# 06_SDIO.net
KiCad netlist of a schematic drawn in Altium Designer
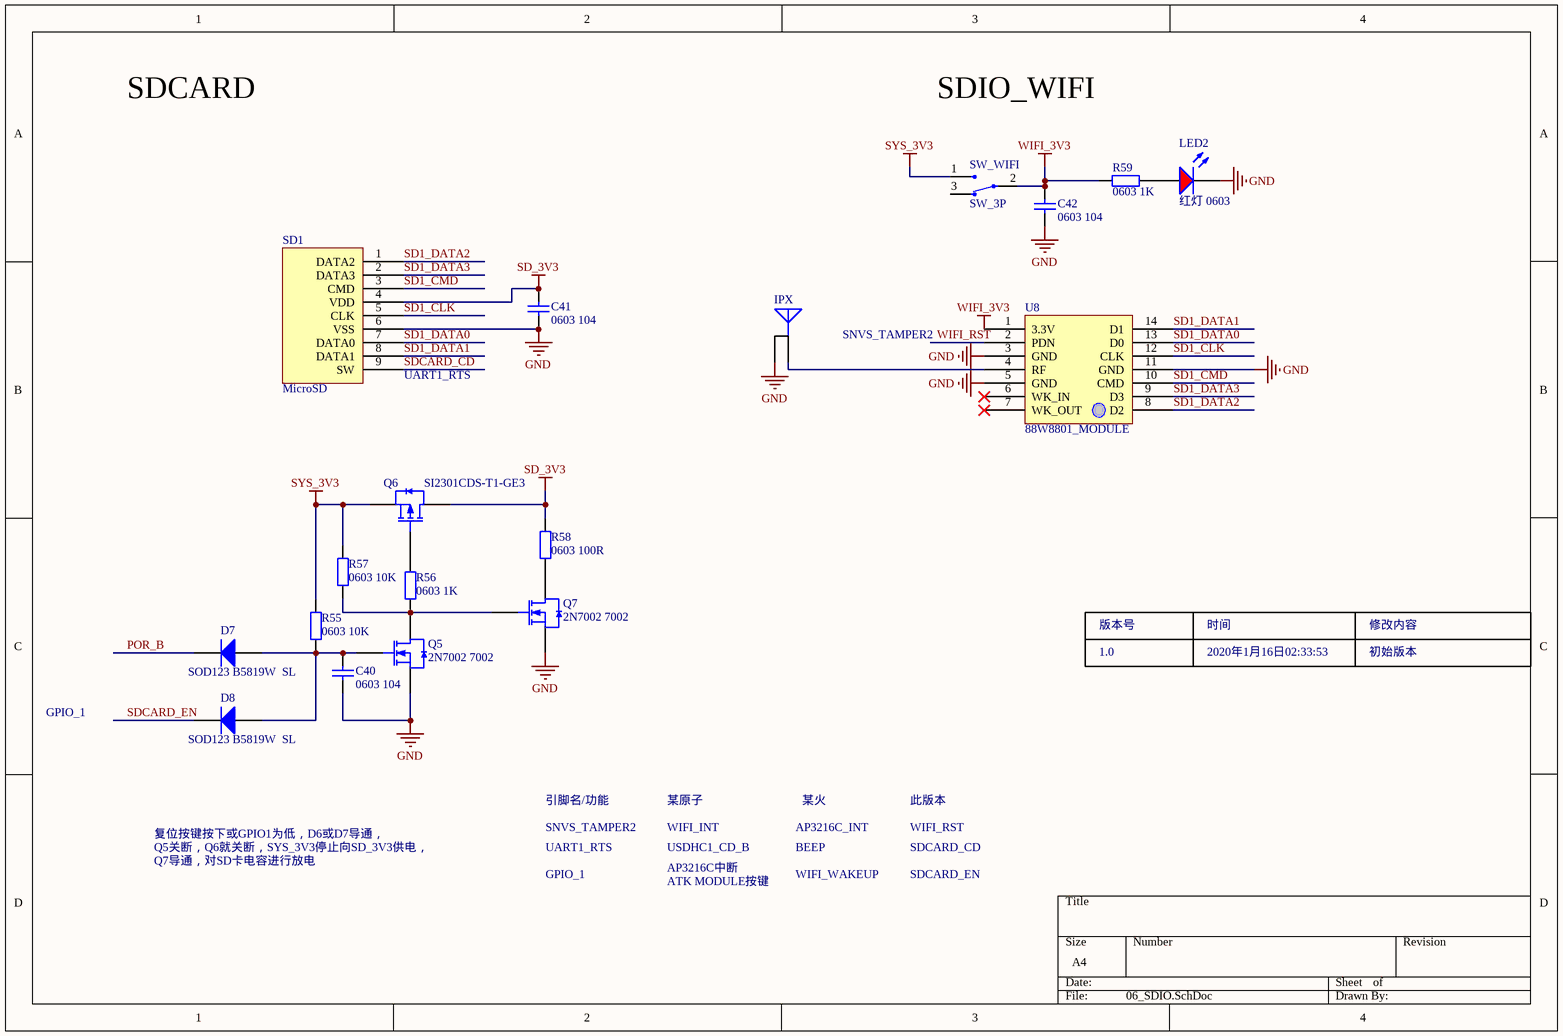
[diagram p0: 06_SDIO.SchDoc]

(export (version "E")
  (design (tool "Eeschema 10.0.6"))
  (components
    (comp (ref "C40")
      (value "0603 104")
      (footprint "LC-0603_C")
      (description "贴片电容")
      (libsource (lib "JLC") (part "0603 1.5nF (152) 10% 50V"))
    )
    (comp (ref "C41")
      (value "0603 104")
      (footprint "LC-0603_C")
      (description "贴片电容")
      (libsource (lib "JLC") (part "0603 1.5nF (152) 10% 50V"))
    )
    (comp (ref "C42")
      (value "0603 104")
      (footprint "LC-0603_C")
      (description "贴片电容")
      (libsource (lib "JLC") (part "0603 1.5nF (152) 10% 50V"))
    )
    (comp (ref "D7")
      (value "SOD123 B5819W  SL")
      (footprint "LC-SOD-123")
      (description "肖特基二极管")
      (libsource (lib "JLC") (part "SOD-123 B5819W  SL"))
    )
    (comp (ref "D8")
      (value "SOD123 B5819W  SL")
      (footprint "LC-SOD-123")
      (description "肖特基二极管")
      (libsource (lib "JLC") (part "SOD-123 B5819W  SL"))
    )
    (comp (ref "IPX") (value "~") (footprint "IPX") (libsource (lib "Integrated_Library2") (part "RF_ANT")))
    (comp (ref "LED2")
      (value "红灯 0603")
      (footprint "LC-0603_LED_S1")
      (description "发光二极管")
      (libsource (lib "JLC") (part "0603 红灯"))
    )
    (comp (ref "Q5")
      (value "2N7002 7002")
      (footprint "LC-SOT-23(SOT-23-3)")
      (description "MOS(场效应管)")
      (libsource (lib "JLC") (part "2N7002 7002"))
    )
    (comp (ref "Q6")
      (value "SI2301CDS-T1-GE3")
      (footprint "LC-SOT-23(SOT-23-3)")
      (description "MOS(场效应管)")
      (libsource (lib "JLC") (part "SI2301CDS-T1-GE3"))
    )
    (comp (ref "Q7")
      (value "2N7002 7002")
      (footprint "LC-SOT-23(SOT-23-3)")
      (description "MOS(场效应管)")
      (libsource (lib "JLC") (part "2N7002 7002"))
    )
    (comp (ref "R55")
      (value "0603 10K")
      (footprint "LC-0603_R")
      (description "贴片电阻")
      (libsource (lib "") (part "0603 1.1KΩ (1101) 1%_1"))
    )
    (comp (ref "R56")
      (value "0603 1K")
      (footprint "LC-0603_R")
      (description "贴片电阻")
      (libsource (lib "") (part "0603 1.1KΩ (1101) 1%_1"))
    )
    (comp (ref "R57")
      (value "0603 10K")
      (footprint "LC-0603_R")
      (description "贴片电阻")
      (libsource (lib "") (part "0603 1.1KΩ (1101) 1%_1"))
    )
    (comp (ref "R58")
      (value "0603 100R")
      (footprint "LC-0603_R")
      (description "贴片电阻")
      (libsource (lib "") (part "0603 1.1KΩ (1101) 1%_1"))
    )
    (comp (ref "R59")
      (value "0603 1K")
      (footprint "LC-0603_R")
      (description "贴片电阻")
      (libsource (lib "JLC") (part "0603 1.1KΩ (1101) 1%"))
    )
    (comp (ref "SD1")
      (value "MicroSD")
      (footprint "MICROSD_PUSH")
      (libsource (lib "Integrated_Library2") (part "MicroSD"))
    )
    (comp (ref "SW_WIFI")
      (value "SW_3P")
      (footprint "SW_3P")
      (libsource (lib "Integrated_Library2") (part "SW_3P"))
    )
    (comp (ref "U8")
      (value "88W8801_MODULE")
      (footprint "88W8801_MODULE")
      (libsource (lib "Integrated_Library2") (part "88W8801_MODULE"))
    )
  )
  (nets
    (net (code "1") (name "/POR_B") (class "Default")
      (node (ref "D7") (pin "2") (pinfunction "K_2") (pintype "passive"))
    )
    (net (code "2") (name "/SD1_CLK") (class "Default")
      (node (ref "SD1") (pin "5") (pinfunction "CLK_5") (pintype "passive"))
      (node (ref "U8") (pin "12") (pinfunction "CLK_12") (pintype "passive"))
    )
    (net (code "3") (name "/SD1_CMD") (class "Default")
      (node (ref "SD1") (pin "3") (pinfunction "CMD_3") (pintype "passive"))
      (node (ref "U8") (pin "10") (pinfunction "CMD_10") (pintype "passive"))
    )
    (net (code "4") (name "/SD1_DATA0") (class "Default")
      (node (ref "SD1") (pin "7") (pinfunction "DATA0_7") (pintype "passive"))
      (node (ref "U8") (pin "13") (pinfunction "D0_13") (pintype "passive"))
    )
    (net (code "5") (name "/SD1_DATA1") (class "Default")
      (node (ref "SD1") (pin "8") (pinfunction "DATA1_8") (pintype "passive"))
      (node (ref "U8") (pin "14") (pinfunction "D1_14") (pintype "passive"))
    )
    (net (code "6") (name "/SD1_DATA2") (class "Default")
      (node (ref "SD1") (pin "1") (pinfunction "DATA2_1") (pintype "passive"))
      (node (ref "U8") (pin "8") (pinfunction "D2_8") (pintype "passive"))
    )
    (net (code "7") (name "/SD1_DATA3") (class "Default")
      (node (ref "SD1") (pin "2") (pinfunction "DATA3_2") (pintype "passive"))
      (node (ref "U8") (pin "9") (pinfunction "D3_9") (pintype "passive"))
    )
    (net (code "8") (name "/SDCARD_CD") (class "Default")
      (node (ref "SD1") (pin "9") (pinfunction "SW_9") (pintype "passive"))
    )
    (net (code "9") (name "/SDCARD_EN") (class "Default")
      (node (ref "D8") (pin "2") (pinfunction "K_2") (pintype "passive"))
    )
    (net (code "10") (name "/WIFI_RST") (class "Default")
      (node (ref "U8") (pin "2") (pinfunction "PDN_2") (pintype "passive"))
    )
    (net (code "11") (name "GND") (class "Default")
      (node (ref "C40") (pin "2") (pinfunction "2_2") (pintype "passive"))
      (node (ref "C41") (pin "2") (pinfunction "2_2") (pintype "passive"))
      (node (ref "C42") (pin "2") (pinfunction "2_2") (pintype "passive"))
      (node (ref "IPX") (pin "2") (pinfunction "GND_2") (pintype "passive"))
      (node (ref "LED2") (pin "K") (pinfunction "K_K") (pintype "passive"))
      (node (ref "Q5") (pin "2") (pinfunction "S_2") (pintype "passive"))
      (node (ref "Q7") (pin "2") (pinfunction "S_2") (pintype "passive"))
      (node (ref "SD1") (pin "6") (pinfunction "VSS_6") (pintype "passive"))
      (node (ref "U8") (pin "11") (pinfunction "GND_11") (pintype "passive"))
      (node (ref "U8") (pin "3") (pinfunction "GND_3") (pintype "passive"))
      (node (ref "U8") (pin "5") (pinfunction "GND_5") (pintype "passive"))
    )
    (net (code "12") (name "Net-(D7-A)") (class "Default")
      (node (ref "C40") (pin "1") (pinfunction "1_1") (pintype "passive"))
      (node (ref "D7") (pin "1") (pinfunction "A_1") (pintype "passive"))
      (node (ref "D8") (pin "1") (pinfunction "A_1") (pintype "passive"))
      (node (ref "Q5") (pin "1") (pinfunction "G_1") (pintype "passive"))
      (node (ref "R55") (pin "2") (pinfunction "2_2") (pintype "passive"))
    )
    (net (code "13") (name "Net-(IPX-RF)") (class "Default")
      (node (ref "IPX") (pin "1") (pinfunction "RF_1") (pintype "passive"))
      (node (ref "U8") (pin "4") (pinfunction "RF_4") (pintype "passive"))
    )
    (net (code "14") (name "Net-(LED2-PadA)") (class "Default")
      (node (ref "LED2") (pin "A") (pinfunction "A_A") (pintype "passive"))
      (node (ref "R59") (pin "2") (pinfunction "2_2") (pintype "passive"))
    )
    (net (code "15") (name "Net-(Q5-D)") (class "Default")
      (node (ref "Q5") (pin "3") (pinfunction "D_3") (pintype "passive"))
      (node (ref "Q7") (pin "1") (pinfunction "G_1") (pintype "passive"))
      (node (ref "R56") (pin "2") (pinfunction "2_2") (pintype "passive"))
      (node (ref "R57") (pin "2") (pinfunction "2_2") (pintype "passive"))
    )
    (net (code "16") (name "Net-(Q6-G)") (class "Default")
      (node (ref "Q6") (pin "1") (pinfunction "G_1") (pintype "passive"))
      (node (ref "R56") (pin "1") (pinfunction "1_1") (pintype "passive"))
    )
    (net (code "17") (name "Net-(Q7-D)") (class "Default")
      (node (ref "Q7") (pin "3") (pinfunction "D_3") (pintype "passive"))
      (node (ref "R58") (pin "2") (pinfunction "2_2") (pintype "passive"))
    )
    (net (code "18") (name "SD_3V3") (class "Default")
      (node (ref "C41") (pin "1") (pinfunction "1_1") (pintype "passive"))
      (node (ref "Q6") (pin "3") (pinfunction "D_3") (pintype "passive"))
      (node (ref "R58") (pin "1") (pinfunction "1_1") (pintype "passive"))
      (node (ref "SD1") (pin "4") (pinfunction "VDD_4") (pintype "passive"))
    )
    (net (code "19") (name "SYS_3V3") (class "Default")
      (node (ref "Q6") (pin "2") (pinfunction "S_2") (pintype "passive"))
      (node (ref "R55") (pin "1") (pinfunction "1_1") (pintype "passive"))
      (node (ref "R57") (pin "1") (pinfunction "1_1") (pintype "passive"))
      (node (ref "SW_WIFI") (pin "1") (pinfunction "1_1") (pintype "passive"))
    )
    (net (code "20") (name "WIFI_3V3") (class "Default")
      (node (ref "C42") (pin "1") (pinfunction "1_1") (pintype "passive"))
      (node (ref "R59") (pin "1") (pinfunction "1_1") (pintype "passive"))
      (node (ref "SW_WIFI") (pin "2") (pinfunction "2_2") (pintype "passive"))
      (node (ref "U8") (pin "1") (pinfunction "3.3V_1") (pintype "passive"))
    )
    (net (code "21") (name "unconnected-(SW_WIFI-Pad3)") (class "Default")
      (node (ref "SW_WIFI") (pin "3") (pinfunction "3_3") (pintype "passive"))
    )
    (net (code "22") (name "unconnected-(U8-WK_IN-Pad6)") (class "Default")
      (node (ref "U8") (pin "6") (pinfunction "WK_IN_6") (pintype "passive+no_connect"))
    )
    (net (code "23") (name "unconnected-(U8-WK_OUT-Pad7)") (class "Default")
      (node (ref "U8") (pin "7") (pinfunction "WK_OUT_7") (pintype "passive+no_connect"))
    )
  )
)
